# electron_v010.net
KiCad netlist of a schematic drawn in EAGLE
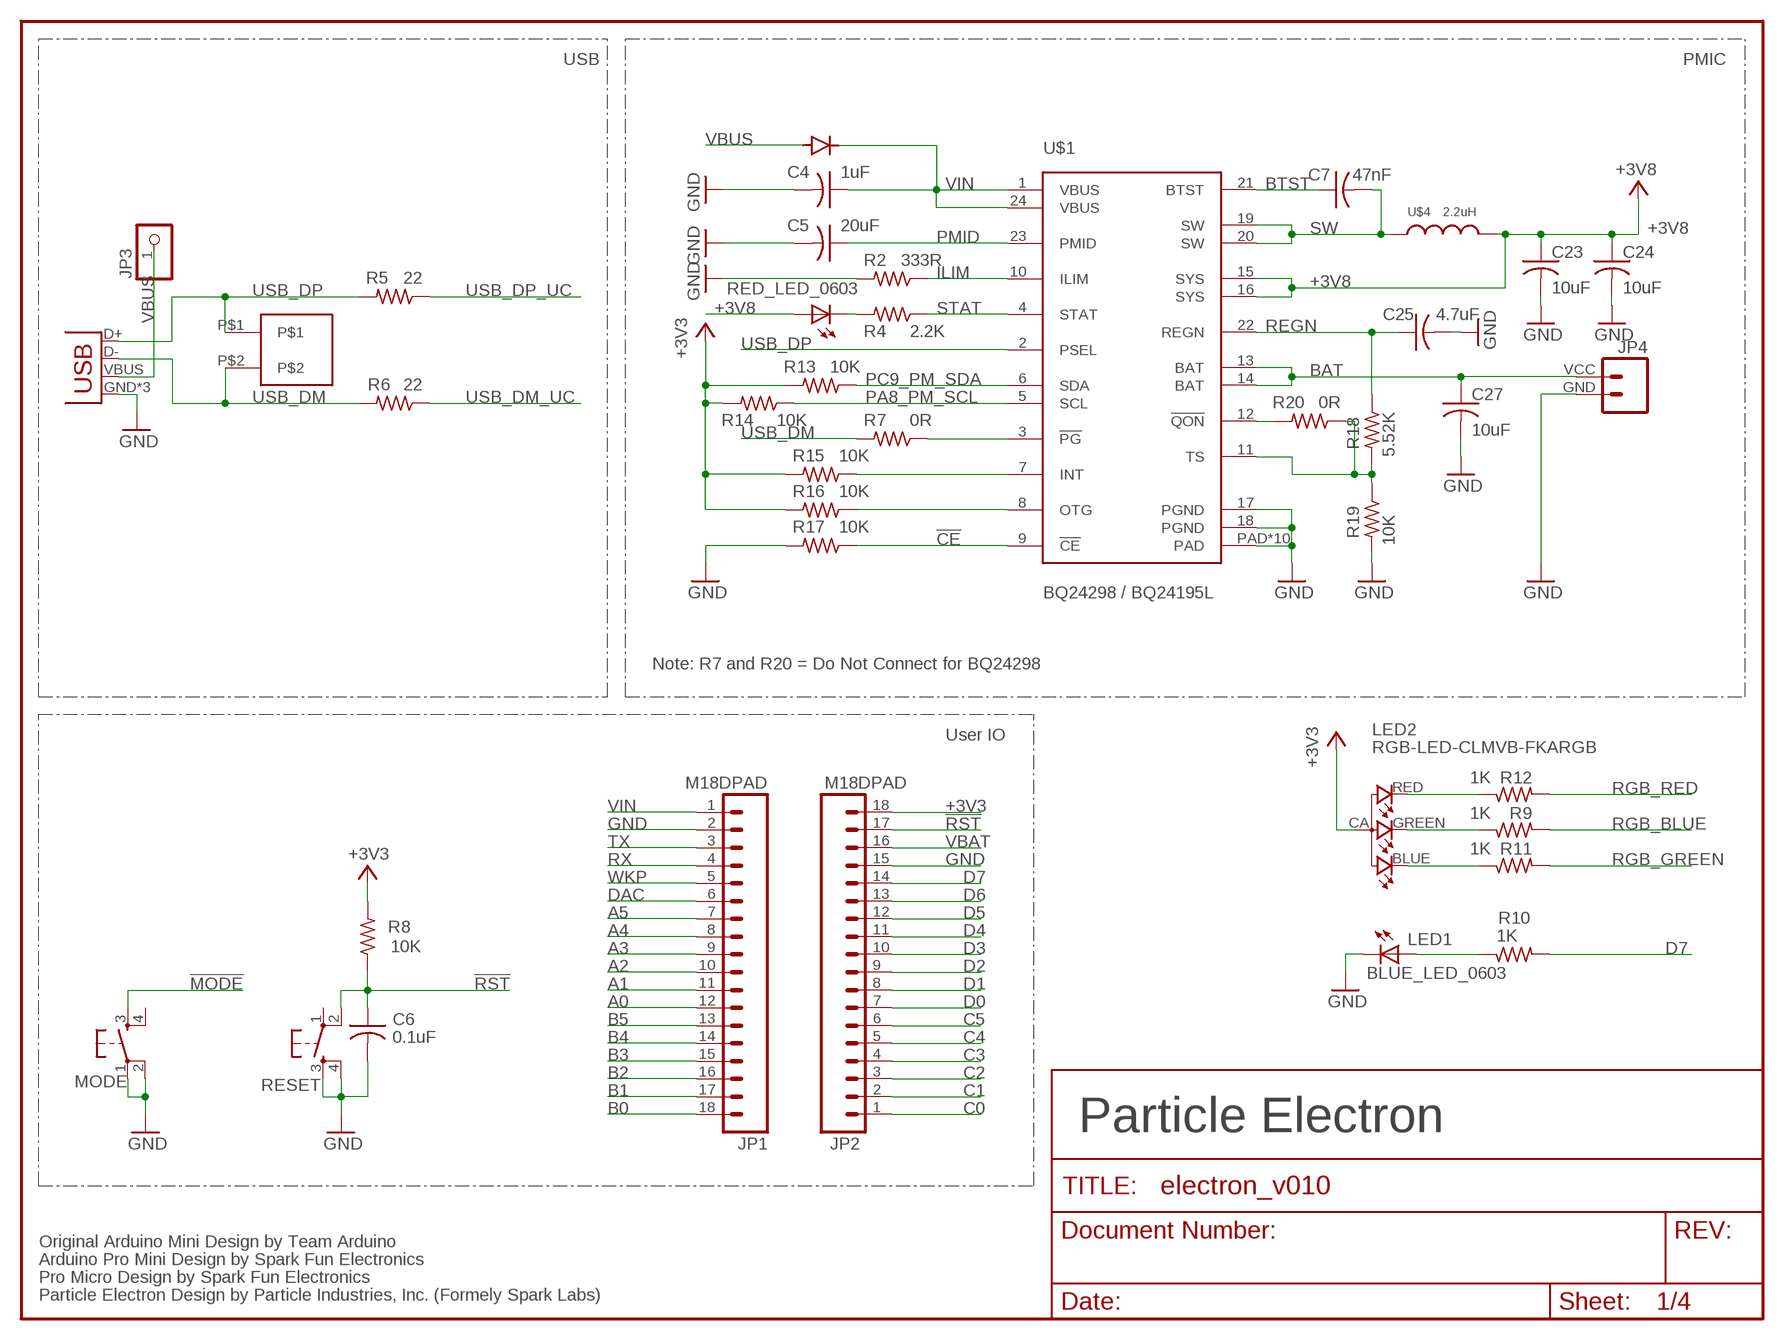
[diagram p0: schematic, sheet 1]
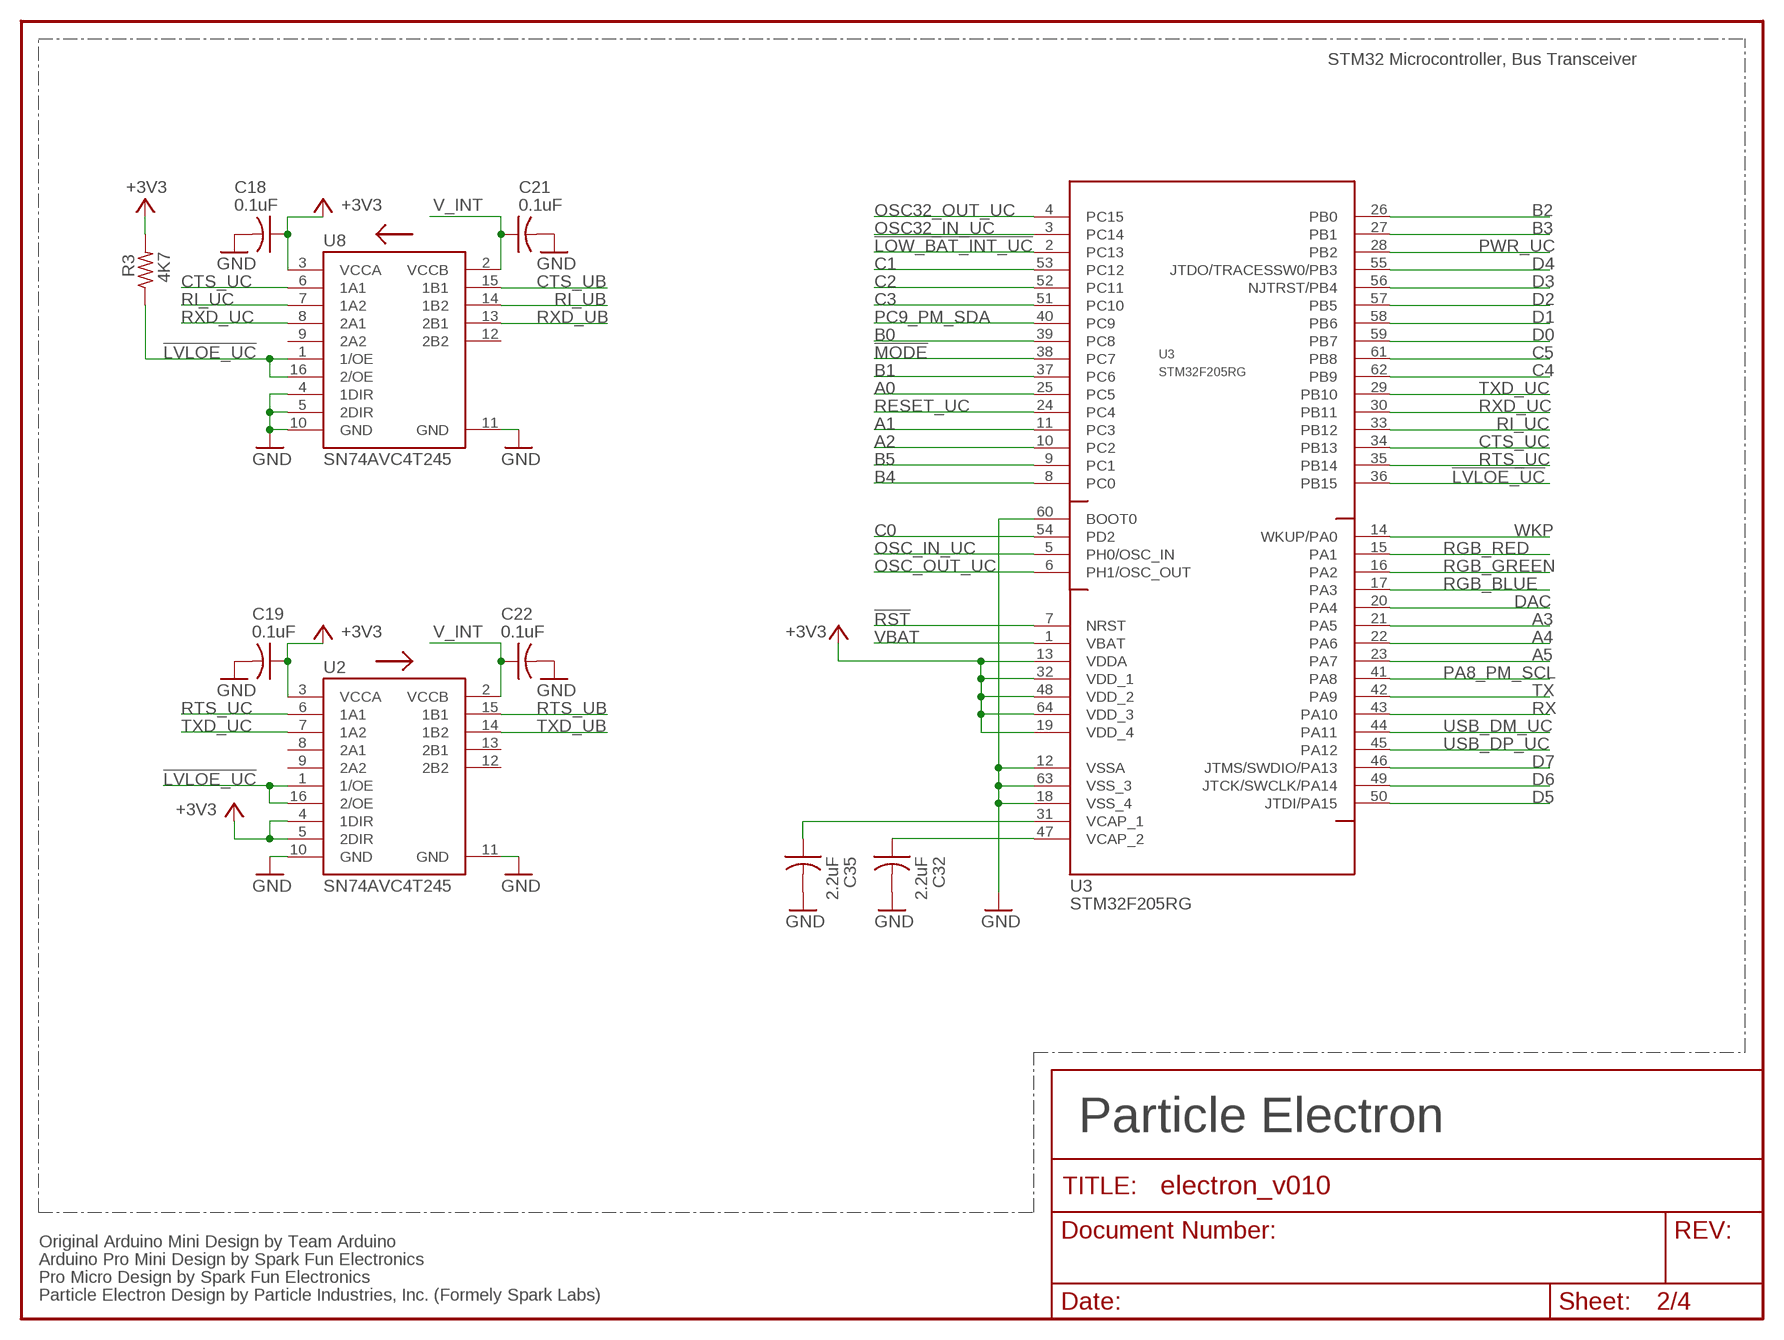
[diagram p1: schematic, sheet 2]
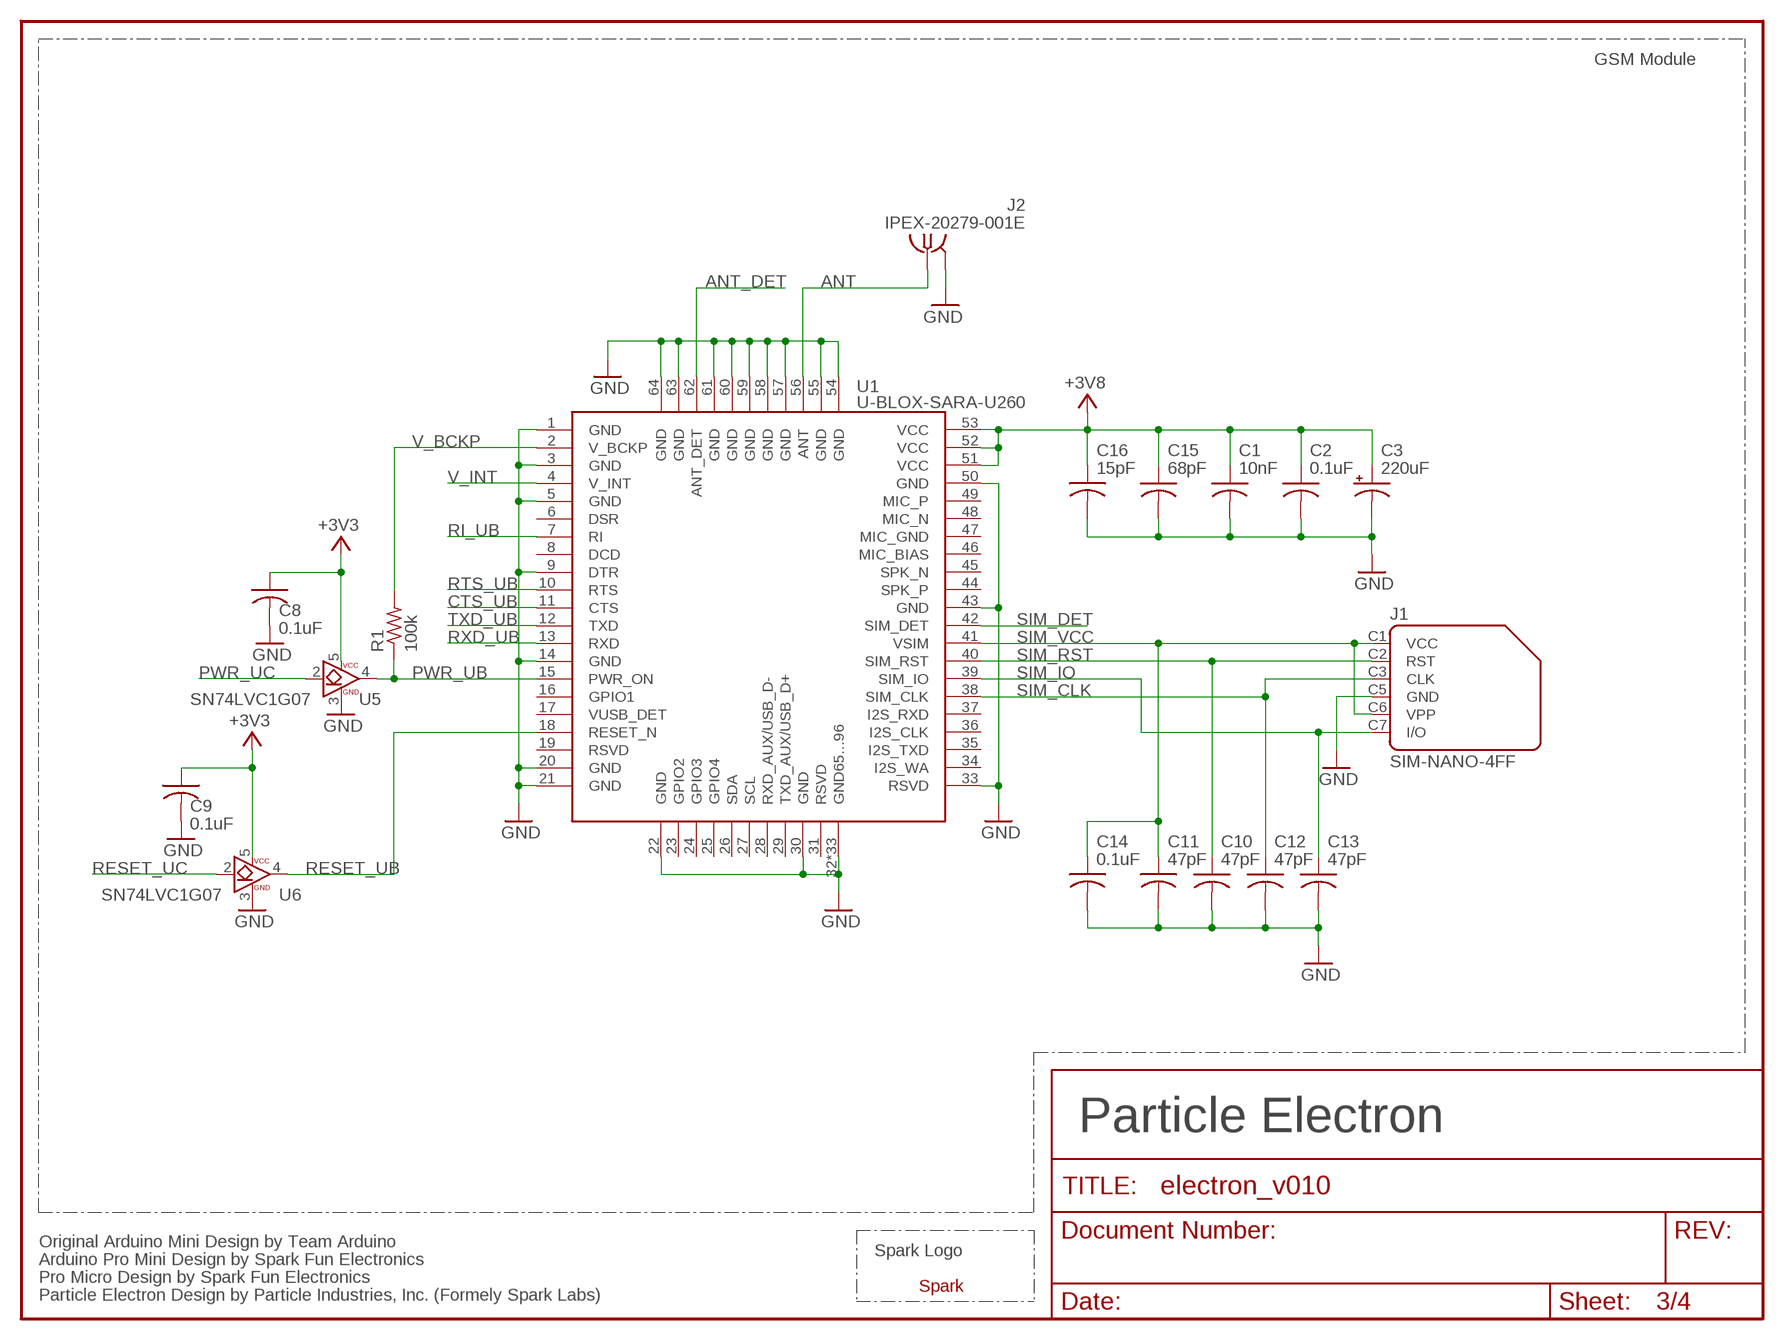
[diagram p2: schematic, sheet 3]
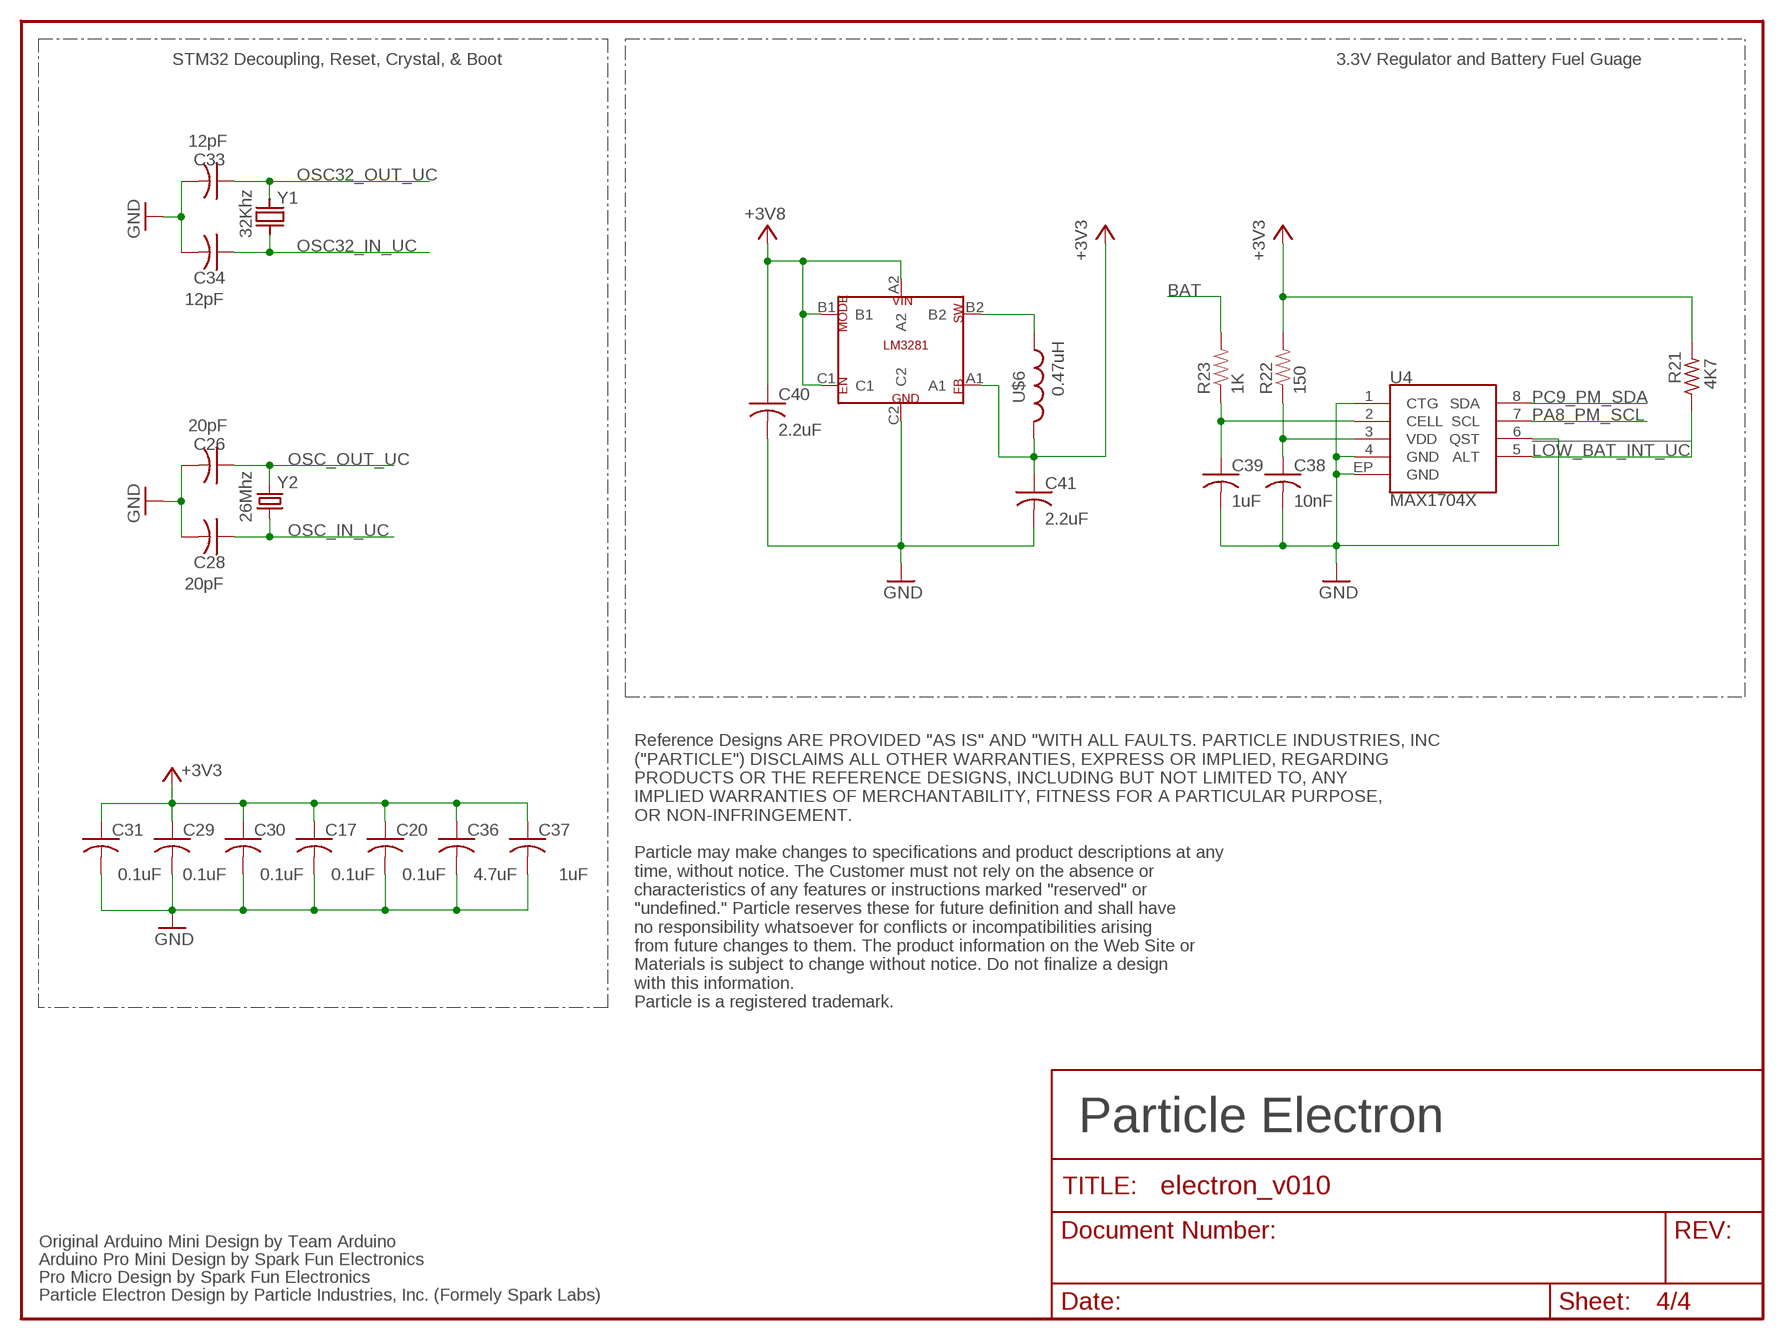
[diagram p3: schematic, sheet 4]

(export (version "E")
  (design (tool "Eeschema 10.0.6"))
  (components
    (comp (ref "C17")
      (value "0.1uF")
      (footprint "eagle-import:C0402_B")
      (libsource (lib "eagle-import") (part "C-US"))
    )
    (comp (ref "C20")
      (value "0.1uF")
      (footprint "eagle-import:C0402_B")
      (libsource (lib "eagle-import") (part "C-US"))
    )
    (comp (ref "C26")
      (value "20pF")
      (footprint "eagle-import:C0402_B")
      (libsource (lib "eagle-import") (part "C-US"))
    )
    (comp (ref "C28")
      (value "20pF")
      (footprint "eagle-import:C0402_B")
      (libsource (lib "eagle-import") (part "C-US"))
    )
    (comp (ref "C29")
      (value "0.1uF")
      (footprint "eagle-import:C0402_B")
      (libsource (lib "eagle-import") (part "C-US"))
    )
    (comp (ref "C30")
      (value "0.1uF")
      (footprint "eagle-import:C0402_B")
      (libsource (lib "eagle-import") (part "C-US"))
    )
    (comp (ref "C31")
      (value "0.1uF")
      (footprint "eagle-import:C0402_B")
      (libsource (lib "eagle-import") (part "C-US"))
    )
    (comp (ref "C33")
      (value "12pF")
      (footprint "eagle-import:C0402_B")
      (libsource (lib "eagle-import") (part "C-US"))
    )
    (comp (ref "C34")
      (value "12pF")
      (footprint "eagle-import:C0402_B")
      (libsource (lib "eagle-import") (part "C-US"))
    )
    (comp (ref "C36")
      (value "4.7uF")
      (footprint "eagle-import:C0402_B")
      (libsource (lib "eagle-import") (part "C-US"))
    )
    (comp (ref "C37")
      (value "1uF")
      (footprint "eagle-import:C0402_B")
      (libsource (lib "eagle-import") (part "C-US"))
    )
    (comp (ref "C38")
      (value "10nF")
      (footprint "eagle-import:C0402_B")
      (libsource (lib "eagle-import") (part "C-US"))
    )
    (comp (ref "C39")
      (value "1uF")
      (footprint "eagle-import:C0402_B")
      (libsource (lib "eagle-import") (part "C-US"))
    )
    (comp (ref "C40")
      (value "2.2uF")
      (footprint "eagle-import:C0603_B")
      (libsource (lib "eagle-import") (part "C-US0603"))
    )
    (comp (ref "C41")
      (value "2.2uF")
      (footprint "eagle-import:C0603_B")
      (libsource (lib "eagle-import") (part "C-US0603"))
    )
    (comp (ref "R21")
      (value "4K7")
      (footprint "eagle-import:R0402_B")
      (libsource (lib "eagle-import") (part "R-US_"))
    )
    (comp (ref "R22")
      (value "150")
      (footprint "eagle-import:0603-RES")
      (libsource (lib "eagle-import") (part "RESISTOR0603-RES"))
    )
    (comp (ref "R23")
      (value "1K")
      (footprint "eagle-import:0603-RES")
      (libsource (lib "eagle-import") (part "RESISTOR0603-RES"))
    )
    (comp (ref "U$5")
      (value "LM3281_DSBGA")
      (footprint "eagle-import:DSBGA")
      (libsource (lib "eagle-import") (part "LM3281_DSBGA"))
    )
    (comp (ref "U$6")
      (value "0.47uH")
      (footprint "eagle-import:INDUCTOR-0805")
      (libsource (lib "eagle-import") (part "INDUCTORG"))
    )
    (comp (ref "U4")
      (value "MAX1704X")
      (footprint "eagle-import:TDFN-8")
      (libsource (lib "eagle-import") (part "MAX1704X"))
    )
    (comp (ref "Y1")
      (value "32Khz")
      (footprint "eagle-import:FC135")
      (libsource (lib "eagle-import") (part "Q_FC135"))
    )
    (comp (ref "Y2")
      (value "26Mhz")
      (footprint "eagle-import:CRYSTAL-SMD-5X3")
      (libsource (lib "eagle-import") (part "CRYSTAL5X3"))
    )
    (comp (ref "C1")
      (value "10nF")
      (footprint "eagle-import:C0402_B")
      (libsource (lib "eagle-import") (part "C-US"))
    )
    (comp (ref "C2")
      (value "0.1uF")
      (footprint "eagle-import:C0402_B")
      (libsource (lib "eagle-import") (part "C-US"))
    )
    (comp (ref "C3")
      (value "220uF")
      (footprint "eagle-import:C_6032-28R")
      (libsource (lib "eagle-import") (part "CPOL-USC/6032-28R"))
    )
    (comp (ref "C8")
      (value "0.1uF")
      (footprint "eagle-import:C0402_B")
      (libsource (lib "eagle-import") (part "C-US"))
    )
    (comp (ref "C9")
      (value "0.1uF")
      (footprint "eagle-import:C0402_B")
      (libsource (lib "eagle-import") (part "C-US"))
    )
    (comp (ref "C10")
      (value "47pF")
      (footprint "eagle-import:C0402_B")
      (libsource (lib "eagle-import") (part "C-US"))
    )
    (comp (ref "C11")
      (value "47pF")
      (footprint "eagle-import:C0402_B")
      (libsource (lib "eagle-import") (part "C-US"))
    )
    (comp (ref "C12")
      (value "47pF")
      (footprint "eagle-import:C0402_B")
      (libsource (lib "eagle-import") (part "C-US"))
    )
    (comp (ref "C13")
      (value "47pF")
      (footprint "eagle-import:C0402_B")
      (libsource (lib "eagle-import") (part "C-US"))
    )
    (comp (ref "C14")
      (value "0.1uF")
      (footprint "eagle-import:C0402_B")
      (libsource (lib "eagle-import") (part "C-US"))
    )
    (comp (ref "C15")
      (value "68pF")
      (footprint "eagle-import:C0402_B")
      (libsource (lib "eagle-import") (part "C-US"))
    )
    (comp (ref "C16")
      (value "15pF")
      (footprint "eagle-import:C0402_B")
      (libsource (lib "eagle-import") (part "C-US"))
    )
    (comp (ref "J1")
      (value "SIM-NANO-4FF")
      (footprint "eagle-import:GCT-SIM8100")
      (libsource (lib "eagle-import") (part "SIM-NANO-4FF"))
    )
    (comp (ref "J2")
      (value "IPEX-20279-001E")
      (footprint "eagle-import:IPEX-20279-001E")
      (libsource (lib "eagle-import") (part "IPEX-20279-001E"))
    )
    (comp (ref "R1")
      (value "100k")
      (footprint "eagle-import:R0402_B")
      (libsource (lib "eagle-import") (part "R-US_"))
    )
    (comp (ref "U$2")
      (value "SPARK_LOGO2")
      (footprint "eagle-import:SPARK_LOGO2")
      (libsource (lib "eagle-import") (part "SPARK_LOGO2"))
    )
    (comp (ref "U1")
      (value "U-BLOX-SARA-U260")
      (footprint "eagle-import:U-BLOX-SARA-U2")
      (libsource (lib "eagle-import") (part "U-BLOX-SARA-U260"))
    )
    (comp (ref "U5")
      (value "SN74LVC1G07")
      (footprint "eagle-import:SC-70-5")
      (libsource (lib "eagle-import") (part "SN74LVC1G07"))
    )
    (comp (ref "U6")
      (value "SN74LVC1G07")
      (footprint "eagle-import:SC-70-5")
      (libsource (lib "eagle-import") (part "SN74LVC1G07"))
    )
    (comp (ref "C18")
      (value "0.1uF")
      (footprint "eagle-import:C0402_B")
      (libsource (lib "eagle-import") (part "C-US"))
    )
    (comp (ref "C19")
      (value "0.1uF")
      (footprint "eagle-import:C0402_B")
      (libsource (lib "eagle-import") (part "C-US"))
    )
    (comp (ref "C21")
      (value "0.1uF")
      (footprint "eagle-import:C0402_B")
      (libsource (lib "eagle-import") (part "C-US"))
    )
    (comp (ref "C22")
      (value "0.1uF")
      (footprint "eagle-import:C0402_B")
      (libsource (lib "eagle-import") (part "C-US"))
    )
    (comp (ref "C32")
      (value "2.2uF")
      (footprint "eagle-import:C0402_B")
      (libsource (lib "eagle-import") (part "C-US"))
    )
    (comp (ref "C35")
      (value "2.2uF")
      (footprint "eagle-import:C0402_B")
      (libsource (lib "eagle-import") (part "C-US"))
    )
    (comp (ref "R3")
      (value "4K7")
      (footprint "eagle-import:R0402_B")
      (libsource (lib "eagle-import") (part "R-US_"))
    )
    (comp (ref "U2")
      (value "SN74AVC4T245")
      (footprint "eagle-import:UFQFN-16")
      (libsource (lib "eagle-import") (part "SN74AVC4T245"))
    )
    (comp (ref "U3")
      (value "STM32F205RG")
      (footprint "eagle-import:LQFP64")
      (libsource (lib "eagle-import") (part "STM32F20XR"))
    )
    (comp (ref "U8")
      (value "SN74AVC4T245")
      (footprint "eagle-import:UFQFN-16")
      (libsource (lib "eagle-import") (part "SN74AVC4T245"))
    )
    (comp (ref "BLUE_LED_0603")
      (value "LED0603")
      (footprint "eagle-import:LED-0603")
      (libsource (lib "eagle-import") (part "LED0603"))
    )
    (comp (ref "C4")
      (value "1uF")
      (footprint "eagle-import:C0603_B")
      (libsource (lib "eagle-import") (part "C-US0603"))
    )
    (comp (ref "C5")
      (value "20uF")
      (footprint "eagle-import:C0603_B")
      (libsource (lib "eagle-import") (part "C-US0603"))
    )
    (comp (ref "C6")
      (value "0.1uF")
      (footprint "eagle-import:C0402_B")
      (libsource (lib "eagle-import") (part "C-US"))
    )
    (comp (ref "C7")
      (value "47nF")
      (footprint "eagle-import:C0402_B")
      (libsource (lib "eagle-import") (part "C-US"))
    )
    (comp (ref "C23")
      (value "10uF")
      (footprint "eagle-import:C0603_B")
      (libsource (lib "eagle-import") (part "C-US0603"))
    )
    (comp (ref "C24")
      (value "10uF")
      (footprint "eagle-import:C0603_B")
      (libsource (lib "eagle-import") (part "C-US0603"))
    )
    (comp (ref "C25")
      (value "4.7uF")
      (footprint "eagle-import:C0603_B")
      (libsource (lib "eagle-import") (part "C-US0603"))
    )
    (comp (ref "C27")
      (value "10uF")
      (footprint "eagle-import:C0603_B")
      (libsource (lib "eagle-import") (part "C-US0603"))
    )
    (comp (ref "JP1")
      (value "M18DPAD")
      (footprint "eagle-import:1X18-D-PADS")
      (libsource (lib "eagle-import") (part "M18DPAD"))
    )
    (comp (ref "JP2")
      (value "M18DPAD")
      (footprint "eagle-import:1X18-D-PADS")
      (libsource (lib "eagle-import") (part "M18DPAD"))
    )
    (comp (ref "JP3")
      (value "PINHD-1X1")
      (footprint "eagle-import:1X01")
      (libsource (lib "eagle-import") (part "PINHD-1X1"))
    )
    (comp (ref "JP4")
      (value "M024UCON-15767")
      (footprint "eagle-import:JST-2-SMD-VERT")
      (libsource (lib "eagle-import") (part "M024UCON-15767"))
    )
    (comp (ref "LED2")
      (value "RGB-LED-CLMVB-FKARGB")
      (footprint "eagle-import:PLCC4-2MM-RGB")
      (libsource (lib "eagle-import") (part "RGB-LED-CLMVB-FKARGB"))
    )
    (comp (ref "MODE")
      (value "KMR211GLFS")
      (footprint "eagle-import:TACTILE_SWITCH_SMD")
      (libsource (lib "eagle-import") (part "TAC_SWITCHSMD"))
    )
    (comp (ref "R2")
      (value "333R")
      (footprint "eagle-import:R0402_B")
      (libsource (lib "eagle-import") (part "R-US_"))
    )
    (comp (ref "R4")
      (value "2.2K")
      (footprint "eagle-import:R0402_B")
      (libsource (lib "eagle-import") (part "R-US_"))
    )
    (comp (ref "R5")
      (value "22")
      (footprint "eagle-import:R0402_B")
      (libsource (lib "eagle-import") (part "R-US_"))
    )
    (comp (ref "R6")
      (value "22")
      (footprint "eagle-import:R0402_B")
      (libsource (lib "eagle-import") (part "R-US_"))
    )
    (comp (ref "R7")
      (value "0R")
      (footprint "eagle-import:R0402_B")
      (libsource (lib "eagle-import") (part "R-US_"))
    )
    (comp (ref "R8")
      (value "10K")
      (footprint "eagle-import:R0402_B")
      (libsource (lib "eagle-import") (part "R-US_"))
    )
    (comp (ref "R9")
      (value "1K")
      (footprint "eagle-import:R0402_B")
      (libsource (lib "eagle-import") (part "R-US_"))
    )
    (comp (ref "R10")
      (value "1K")
      (footprint "eagle-import:R0402_B")
      (libsource (lib "eagle-import") (part "R-US_"))
    )
    (comp (ref "R11")
      (value "1K")
      (footprint "eagle-import:R0402_B")
      (libsource (lib "eagle-import") (part "R-US_"))
    )
    (comp (ref "R12")
      (value "1K")
      (footprint "eagle-import:R0402_B")
      (libsource (lib "eagle-import") (part "R-US_"))
    )
    (comp (ref "R13")
      (value "10K")
      (footprint "eagle-import:R0402_B")
      (libsource (lib "eagle-import") (part "R-US_"))
    )
    (comp (ref "R14")
      (value "10K")
      (footprint "eagle-import:R0402_B")
      (libsource (lib "eagle-import") (part "R-US_"))
    )
    (comp (ref "R15")
      (value "10K")
      (footprint "eagle-import:R0402_B")
      (libsource (lib "eagle-import") (part "R-US_"))
    )
    (comp (ref "R16")
      (value "10K")
      (footprint "eagle-import:R0402_B")
      (libsource (lib "eagle-import") (part "R-US_"))
    )
    (comp (ref "R17")
      (value "10K")
      (footprint "eagle-import:R0402_B")
      (libsource (lib "eagle-import") (part "R-US_"))
    )
    (comp (ref "R18")
      (value "5.52K")
      (footprint "eagle-import:R0402_B")
      (libsource (lib "eagle-import") (part "R-US_"))
    )
    (comp (ref "R19")
      (value "10K")
      (footprint "eagle-import:R0402_B")
      (libsource (lib "eagle-import") (part "R-US_"))
    )
    (comp (ref "R20")
      (value "0R")
      (footprint "eagle-import:R0402_B")
      (libsource (lib "eagle-import") (part "R-US_"))
    )
    (comp (ref "RED_LED_0603")
      (value "LED0603")
      (footprint "eagle-import:LED-0603")
      (libsource (lib "eagle-import") (part "LED0603"))
    )
    (comp (ref "RESET")
      (value "KMR211GLFS")
      (footprint "eagle-import:TACTILE_SWITCH_SMD")
      (libsource (lib "eagle-import") (part "TAC_SWITCHSMD"))
    )
    (comp (ref "U$1")
      (value "BQ24298 / BQ24195L")
      (footprint "eagle-import:QFN24")
      (libsource (lib "eagle-import") (part "BQ24298RTWR"))
    )
    (comp (ref "U$3")
      (value "DIODE")
      (footprint "eagle-import:DIODE-DO-220AA(SMP)")
      (libsource (lib "eagle-import") (part "DIODE"))
    )
    (comp (ref "U$4")
      (value "2.2uH")
      (footprint "eagle-import:INDUCTOR-4020")
      (libsource (lib "eagle-import") (part "INDUCTORH"))
    )
    (comp (ref "U$7")
      (value "M02_0.05_HEADER")
      (footprint "eagle-import:M02_0.05_HEADER")
      (libsource (lib "eagle-import") (part "M02_0.05_HEADER"))
    )
    (comp (ref "X1")
      (value "USB-MICROB")
      (footprint "eagle-import:USB-MICROB-SLOT-HOLE")
      (libsource (lib "eagle-import") (part "USBUSB-MICROB-SLOT-HOLE"))
    )
  )
  (nets
    (net (code "1") (name "+3V3") (class "Default")
      (node (ref "C17") (pin "1") (pinfunction "1_1") (pintype "passive"))
      (node (ref "C18") (pin "1") (pinfunction "1_1") (pintype "passive"))
      (node (ref "C19") (pin "1") (pinfunction "1_1") (pintype "passive"))
      (node (ref "C20") (pin "1") (pinfunction "1_1") (pintype "passive"))
      (node (ref "C29") (pin "1") (pinfunction "1_1") (pintype "passive"))
      (node (ref "C30") (pin "1") (pinfunction "1_1") (pintype "passive"))
      (node (ref "C31") (pin "1") (pinfunction "1_1") (pintype "passive"))
      (node (ref "C36") (pin "1") (pinfunction "1_1") (pintype "passive"))
      (node (ref "C37") (pin "1") (pinfunction "1_1") (pintype "passive"))
      (node (ref "C41") (pin "1") (pinfunction "1_1") (pintype "passive"))
      (node (ref "C8") (pin "1") (pinfunction "1_1") (pintype "passive"))
      (node (ref "C9") (pin "1") (pinfunction "1_1") (pintype "passive"))
      (node (ref "JP2") (pin "18") (pinfunction "18_18") (pintype "passive"))
      (node (ref "LED2") (pin "CA") (pinfunction "1_CA") (pintype "passive"))
      (node (ref "R13") (pin "2") (pinfunction "2_2") (pintype "passive"))
      (node (ref "R14") (pin "2") (pinfunction "2_2") (pintype "passive"))
      (node (ref "R15") (pin "2") (pinfunction "2_2") (pintype "passive"))
      (node (ref "R16") (pin "2") (pinfunction "2_2") (pintype "passive"))
      (node (ref "R21") (pin "2") (pinfunction "2_2") (pintype "passive"))
      (node (ref "R22") (pin "2") (pinfunction "2_2") (pintype "passive"))
      (node (ref "R3") (pin "2") (pinfunction "2_2") (pintype "passive"))
      (node (ref "R8") (pin "2") (pinfunction "2_2") (pintype "passive"))
      (node (ref "U$5") (pin "A1") (pinfunction "A1_A1") (pintype "bidirectional"))
      (node (ref "U$6") (pin "2") (pinfunction "2_2") (pintype "passive"))
      (node (ref "U2") (pin "3") (pinfunction "VCCA_3") (pintype "bidirectional"))
      (node (ref "U2") (pin "4") (pinfunction "1DIR_4") (pintype "bidirectional"))
      (node (ref "U2") (pin "5") (pinfunction "2DIR_5") (pintype "bidirectional"))
      (node (ref "U3") (pin "13") (pinfunction "VDDA_13") (pintype "power_in"))
      (node (ref "U3") (pin "19") (pinfunction "VDD_4_19") (pintype "power_in"))
      (node (ref "U3") (pin "32") (pinfunction "VDD_1_32") (pintype "power_in"))
      (node (ref "U3") (pin "48") (pinfunction "VDD_2_48") (pintype "power_in"))
      (node (ref "U3") (pin "64") (pinfunction "VDD_3_64") (pintype "power_in"))
      (node (ref "U5") (pin "5") (pinfunction "VCC_5") (pintype "bidirectional"))
      (node (ref "U6") (pin "5") (pinfunction "VCC_5") (pintype "bidirectional"))
      (node (ref "U8") (pin "3") (pinfunction "VCCA_3") (pintype "bidirectional"))
    )
    (net (code "2") (name "+3V8") (class "Default")
      (node (ref "C1") (pin "1") (pinfunction "1_1") (pintype "passive"))
      (node (ref "C15") (pin "1") (pinfunction "1_1") (pintype "passive"))
      (node (ref "C16") (pin "1") (pinfunction "1_1") (pintype "passive"))
      (node (ref "C2") (pin "1") (pinfunction "1_1") (pintype "passive"))
      (node (ref "C23") (pin "1") (pinfunction "1_1") (pintype "passive"))
      (node (ref "C24") (pin "1") (pinfunction "1_1") (pintype "passive"))
      (node (ref "C3") (pin "+") (pinfunction "+_+") (pintype "passive"))
      (node (ref "C40") (pin "1") (pinfunction "1_1") (pintype "passive"))
      (node (ref "RED_LED_0603") (pin "A") (pinfunction "A_A") (pintype "passive"))
      (node (ref "U$1") (pin "15") (pinfunction "SYS_15") (pintype "power_in"))
      (node (ref "U$1") (pin "16") (pinfunction "SYS_16") (pintype "power_in"))
      (node (ref "U$4") (pin "P$2") (pinfunction "2_P$2") (pintype "passive"))
      (node (ref "U$5") (pin "A2") (pinfunction "A2_A2") (pintype "bidirectional"))
      (node (ref "U$5") (pin "B1") (pinfunction "B1_B1") (pintype "bidirectional"))
      (node (ref "U$5") (pin "C1") (pinfunction "C1_C1") (pintype "bidirectional"))
      (node (ref "U1") (pin "51") (pinfunction "VCC_51") (pintype "bidirectional"))
      (node (ref "U1") (pin "52") (pinfunction "VCC_52") (pintype "bidirectional"))
      (node (ref "U1") (pin "53") (pinfunction "VCC_53") (pintype "bidirectional"))
    )
    (net (code "3") (name "A0") (class "Default")
      (node (ref "JP1") (pin "12") (pinfunction "12_12") (pintype "passive"))
      (node (ref "U3") (pin "25") (pinfunction "PC5_25") (pintype "bidirectional"))
    )
    (net (code "4") (name "A1") (class "Default")
      (node (ref "JP1") (pin "11") (pinfunction "11_11") (pintype "passive"))
      (node (ref "U3") (pin "11") (pinfunction "PC3_11") (pintype "bidirectional"))
    )
    (net (code "5") (name "A2") (class "Default")
      (node (ref "JP1") (pin "10") (pinfunction "10_10") (pintype "passive"))
      (node (ref "U3") (pin "10") (pinfunction "PC2_10") (pintype "bidirectional"))
    )
    (net (code "6") (name "A3") (class "Default")
      (node (ref "JP1") (pin "9") (pinfunction "9_9") (pintype "passive"))
      (node (ref "U3") (pin "21") (pinfunction "PA5_21") (pintype "bidirectional"))
    )
    (net (code "7") (name "A4") (class "Default")
      (node (ref "JP1") (pin "8") (pinfunction "8_8") (pintype "passive"))
      (node (ref "U3") (pin "22") (pinfunction "PA6_22") (pintype "bidirectional"))
    )
    (net (code "8") (name "A5") (class "Default")
      (node (ref "JP1") (pin "7") (pinfunction "7_7") (pintype "passive"))
      (node (ref "U3") (pin "23") (pinfunction "PA7_23") (pintype "bidirectional"))
    )
    (net (code "9") (name "ANT") (class "Default")
      (node (ref "J2") (pin "1") (pinfunction "1_1") (pintype "passive"))
      (node (ref "U1") (pin "56") (pinfunction "ANT_56") (pintype "bidirectional"))
    )
    (net (code "10") (name "ANT_DET") (class "Default")
      (node (ref "U1") (pin "62") (pinfunction "ANT_DET_62") (pintype "bidirectional"))
    )
    (net (code "11") (name "B0") (class "Default")
      (node (ref "JP1") (pin "18") (pinfunction "18_18") (pintype "passive"))
      (node (ref "U3") (pin "39") (pinfunction "PC8_39") (pintype "bidirectional"))
    )
    (net (code "12") (name "B1") (class "Default")
      (node (ref "JP1") (pin "17") (pinfunction "17_17") (pintype "passive"))
      (node (ref "U3") (pin "37") (pinfunction "PC6_37") (pintype "bidirectional"))
    )
    (net (code "13") (name "B2") (class "Default")
      (node (ref "JP1") (pin "16") (pinfunction "16_16") (pintype "passive"))
      (node (ref "U3") (pin "26") (pinfunction "PB0_26") (pintype "bidirectional"))
    )
    (net (code "14") (name "B3") (class "Default")
      (node (ref "JP1") (pin "15") (pinfunction "15_15") (pintype "passive"))
      (node (ref "U3") (pin "27") (pinfunction "PB1_27") (pintype "bidirectional"))
    )
    (net (code "15") (name "B4") (class "Default")
      (node (ref "JP1") (pin "14") (pinfunction "14_14") (pintype "passive"))
      (node (ref "U3") (pin "8") (pinfunction "PC0_8") (pintype "bidirectional"))
    )
    (net (code "16") (name "B5") (class "Default")
      (node (ref "JP1") (pin "13") (pinfunction "13_13") (pintype "passive"))
      (node (ref "U3") (pin "9") (pinfunction "PC1_9") (pintype "bidirectional"))
    )
    (net (code "17") (name "BAT") (class "Default")
      (node (ref "C27") (pin "1") (pinfunction "1_1") (pintype "passive"))
      (node (ref "JP4") (pin "VCC") (pinfunction "2_VCC") (pintype "passive"))
      (node (ref "R23") (pin "2") (pinfunction "2_2") (pintype "passive"))
      (node (ref "U$1") (pin "13") (pinfunction "BAT_13") (pintype "passive"))
      (node (ref "U$1") (pin "14") (pinfunction "BAT_14") (pintype "power_in"))
    )
    (net (code "18") (name "BTST") (class "Default")
      (node (ref "C7") (pin "1") (pinfunction "1_1") (pintype "passive"))
      (node (ref "U$1") (pin "21") (pinfunction "BTST_21") (pintype "bidirectional"))
    )
    (net (code "19") (name "C0") (class "Default")
      (node (ref "JP2") (pin "1") (pinfunction "1_1") (pintype "passive"))
      (node (ref "U3") (pin "54") (pinfunction "PD2_54") (pintype "bidirectional"))
    )
    (net (code "20") (name "C1") (class "Default")
      (node (ref "JP2") (pin "2") (pinfunction "2_2") (pintype "passive"))
      (node (ref "U3") (pin "53") (pinfunction "PC12_53") (pintype "bidirectional"))
    )
    (net (code "21") (name "C2") (class "Default")
      (node (ref "JP2") (pin "3") (pinfunction "3_3") (pintype "passive"))
      (node (ref "U3") (pin "52") (pinfunction "PC11_52") (pintype "bidirectional"))
    )
    (net (code "22") (name "C3") (class "Default")
      (node (ref "JP2") (pin "4") (pinfunction "4_4") (pintype "passive"))
      (node (ref "U3") (pin "51") (pinfunction "PC10_51") (pintype "bidirectional"))
    )
    (net (code "23") (name "C4") (class "Default")
      (node (ref "JP2") (pin "5") (pinfunction "5_5") (pintype "passive"))
      (node (ref "U3") (pin "62") (pinfunction "PB9_62") (pintype "bidirectional"))
    )
    (net (code "24") (name "C5") (class "Default")
      (node (ref "JP2") (pin "6") (pinfunction "6_6") (pintype "passive"))
      (node (ref "U3") (pin "61") (pinfunction "PB8_61") (pintype "bidirectional"))
    )
    (net (code "25") (name "CTS_UB") (class "Default")
      (node (ref "U1") (pin "11") (pinfunction "CTS_11") (pintype "bidirectional"))
      (node (ref "U8") (pin "15") (pinfunction "1B1_15") (pintype "bidirectional"))
    )
    (net (code "26") (name "CTS_UC") (class "Default")
      (node (ref "U3") (pin "34") (pinfunction "PB13_34") (pintype "bidirectional"))
      (node (ref "U8") (pin "6") (pinfunction "1A1_6") (pintype "bidirectional"))
    )
    (net (code "27") (name "D0") (class "Default")
      (node (ref "JP2") (pin "7") (pinfunction "7_7") (pintype "passive"))
      (node (ref "U3") (pin "59") (pinfunction "PB7_59") (pintype "bidirectional"))
    )
    (net (code "28") (name "D1") (class "Default")
      (node (ref "JP2") (pin "8") (pinfunction "8_8") (pintype "passive"))
      (node (ref "U3") (pin "58") (pinfunction "PB6_58") (pintype "bidirectional"))
    )
    (net (code "29") (name "D2") (class "Default")
      (node (ref "JP2") (pin "9") (pinfunction "9_9") (pintype "passive"))
      (node (ref "U3") (pin "57") (pinfunction "PB5_57") (pintype "bidirectional"))
    )
    (net (code "30") (name "D3") (class "Default")
      (node (ref "JP2") (pin "10") (pinfunction "10_10") (pintype "passive"))
      (node (ref "U3") (pin "56") (pinfunction "NJTRST/PB4_56") (pintype "bidirectional"))
    )
    (net (code "31") (name "D4") (class "Default")
      (node (ref "JP2") (pin "11") (pinfunction "11_11") (pintype "passive"))
      (node (ref "U3") (pin "55") (pinfunction "JTDO/TRACESSW0/PB3_55") (pintype "bidirectional"))
    )
    (net (code "32") (name "D5") (class "Default")
      (node (ref "JP2") (pin "12") (pinfunction "12_12") (pintype "passive"))
      (node (ref "U3") (pin "50") (pinfunction "JTDI/PA15_50") (pintype "bidirectional"))
    )
    (net (code "33") (name "D6") (class "Default")
      (node (ref "JP2") (pin "13") (pinfunction "13_13") (pintype "passive"))
      (node (ref "U3") (pin "49") (pinfunction "JTCK/SWCLK/PA14_49") (pintype "bidirectional"))
    )
    (net (code "34") (name "D7") (class "Default")
      (node (ref "JP2") (pin "14") (pinfunction "14_14") (pintype "passive"))
      (node (ref "R10") (pin "2") (pinfunction "2_2") (pintype "passive"))
      (node (ref "U3") (pin "46") (pinfunction "JTMS/SWDIO/PA13_46") (pintype "bidirectional"))
    )
    (net (code "35") (name "DAC") (class "Default")
      (node (ref "JP1") (pin "6") (pinfunction "6_6") (pintype "passive"))
      (node (ref "U3") (pin "20") (pinfunction "PA4_20") (pintype "bidirectional"))
    )
    (net (code "36") (name "GND") (class "Default")
      (node (ref "BLUE_LED_0603") (pin "C") (pinfunction "C_C") (pintype "passive"))
      (node (ref "C1") (pin "2") (pinfunction "2_2") (pintype "passive"))
      (node (ref "C10") (pin "2") (pinfunction "2_2") (pintype "passive"))
      (node (ref "C11") (pin "2") (pinfunction "2_2") (pintype "passive"))
      (node (ref "C12") (pin "2") (pinfunction "2_2") (pintype "passive"))
      (node (ref "C13") (pin "2") (pinfunction "2_2") (pintype "passive"))
      (node (ref "C14") (pin "2") (pinfunction "2_2") (pintype "passive"))
      (node (ref "C15") (pin "2") (pinfunction "2_2") (pintype "passive"))
      (node (ref "C16") (pin "2") (pinfunction "2_2") (pintype "passive"))
      (node (ref "C17") (pin "2") (pinfunction "2_2") (pintype "passive"))
      (node (ref "C18") (pin "2") (pinfunction "2_2") (pintype "passive"))
      (node (ref "C19") (pin "2") (pinfunction "2_2") (pintype "passive"))
      (node (ref "C2") (pin "2") (pinfunction "2_2") (pintype "passive"))
      (node (ref "C20") (pin "2") (pinfunction "2_2") (pintype "passive"))
      (node (ref "C21") (pin "2") (pinfunction "2_2") (pintype "passive"))
      (node (ref "C22") (pin "2") (pinfunction "2_2") (pintype "passive"))
      (node (ref "C23") (pin "2") (pinfunction "2_2") (pintype "passive"))
      (node (ref "C24") (pin "2") (pinfunction "2_2") (pintype "passive"))
      (node (ref "C25") (pin "2") (pinfunction "2_2") (pintype "passive"))
      (node (ref "C26") (pin "2") (pinfunction "2_2") (pintype "passive"))
      (node (ref "C27") (pin "2") (pinfunction "2_2") (pintype "passive"))
      (node (ref "C28") (pin "2") (pinfunction "2_2") (pintype "passive"))
      (node (ref "C29") (pin "2") (pinfunction "2_2") (pintype "passive"))
      (node (ref "C3") (pin "-") (pinfunction "-_-") (pintype "passive"))
      (node (ref "C30") (pin "2") (pinfunction "2_2") (pintype "passive"))
      (node (ref "C31") (pin "2") (pinfunction "2_2") (pintype "passive"))
      (node (ref "C32") (pin "2") (pinfunction "2_2") (pintype "passive"))
      (node (ref "C33") (pin "2") (pinfunction "2_2") (pintype "passive"))
      (node (ref "C34") (pin "2") (pinfunction "2_2") (pintype "passive"))
      (node (ref "C35") (pin "2") (pinfunction "2_2") (pintype "passive"))
      (node (ref "C36") (pin "2") (pinfunction "2_2") (pintype "passive"))
      (node (ref "C37") (pin "2") (pinfunction "2_2") (pintype "passive"))
      (node (ref "C38") (pin "2") (pinfunction "2_2") (pintype "passive"))
      (node (ref "C39") (pin "2") (pinfunction "2_2") (pintype "passive"))
      (node (ref "C4") (pin "2") (pinfunction "2_2") (pintype "passive"))
      (node (ref "C40") (pin "2") (pinfunction "2_2") (pintype "passive"))
      (node (ref "C41") (pin "2") (pinfunction "2_2") (pintype "passive"))
      (node (ref "C5") (pin "2") (pinfunction "2_2") (pintype "passive"))
      (node (ref "C6") (pin "2") (pinfunction "2_2") (pintype "passive"))
      (node (ref "C8") (pin "2") (pinfunction "2_2") (pintype "passive"))
      (node (ref "C9") (pin "2") (pinfunction "2_2") (pintype "passive"))
      (node (ref "J1") (pin "C5") (pinfunction "GND_C5") (pintype "passive"))
      (node (ref "J2") (pin "2@1") (pinfunction "GND_2@1") (pintype "passive"))
      (node (ref "J2") (pin "2@2") (pinfunction "GND_2@2") (pintype "passive"))
      (node (ref "JP1") (pin "2") (pinfunction "2_2") (pintype "passive"))
      (node (ref "JP2") (pin "15") (pinfunction "15_15") (pintype "passive"))
      (node (ref "JP4") (pin "GND") (pinfunction "1_GND") (pintype "passive"))
      (node (ref "MODE") (pin "1") (pinfunction "1_1") (pintype "passive"))
      (node (ref "MODE") (pin "2") (pinfunction "2_2") (pintype "passive"))
      (node (ref "R17") (pin "2") (pinfunction "2_2") (pintype "passive"))
      (node (ref "R19") (pin "2") (pinfunction "2_2") (pintype "passive"))
      (node (ref "R2") (pin "2") (pinfunction "2_2") (pintype "passive"))
      (node (ref "RESET") (pin "3") (pinfunction "3_3") (pintype "passive"))
      (node (ref "RESET") (pin "4") (pinfunction "4_4") (pintype "passive"))
      (node (ref "U$1") (pin "17") (pinfunction "PGND_17") (pintype "passive"))
      (node (ref "U$1") (pin "18") (pinfunction "PGND_18") (pintype "passive"))
      (node (ref "U$1") (pin "PAD") (pinfunction "PAD_PAD") (pintype "power_in"))
      (node (ref "U$1") (pin "PAD@1") (pinfunction "PAD_PAD@1") (pintype "power_in"))
      (node (ref "U$1") (pin "PAD@2") (pinfunction "PAD_PAD@2") (pintype "power_in"))
      (node (ref "U$1") (pin "PAD@3") (pinfunction "PAD_PAD@3") (pintype "power_in"))
      (node (ref "U$1") (pin "PAD@4") (pinfunction "PAD_PAD@4") (pintype "power_in"))
      (node (ref "U$1") (pin "PAD@5") (pinfunction "PAD_PAD@5") (pintype "power_in"))
      (node (ref "U$1") (pin "PAD@6") (pinfunction "PAD_PAD@6") (pintype "power_in"))
      (node (ref "U$1") (pin "PAD@7") (pinfunction "PAD_PAD@7") (pintype "power_in"))
      (node (ref "U$1") (pin "PAD@8") (pinfunction "PAD_PAD@8") (pintype "power_in"))
      (node (ref "U$1") (pin "PAD@9") (pinfunction "PAD_PAD@9") (pintype "power_in"))
      (node (ref "U$5") (pin "C2") (pinfunction "C2_C2") (pintype "bidirectional"))
      (node (ref "U1") (pin "1") (pinfunction "GND_1") (pintype "bidirectional"))
      (node (ref "U1") (pin "14") (pinfunction "GND_14") (pintype "bidirectional"))
      (node (ref "U1") (pin "20") (pinfunction "GND_20") (pintype "bidirectional"))
      (node (ref "U1") (pin "21") (pinfunction "GND_21") (pintype "bidirectional"))
      (node (ref "U1") (pin "22") (pinfunction "GND_22") (pintype "bidirectional"))
      (node (ref "U1") (pin "3") (pinfunction "GND_3") (pintype "bidirectional"))
      (node (ref "U1") (pin "30") (pinfunction "GND_30") (pintype "bidirectional"))
      (node (ref "U1") (pin "32") (pinfunction "GND65...96_32") (pintype "bidirectional"))
      (node (ref "U1") (pin "33") (pinfunction "RSVD_33") (pintype "bidirectional"))
      (node (ref "U1") (pin "43") (pinfunction "GND_43") (pintype "bidirectional"))
      (node (ref "U1") (pin "5") (pinfunction "GND_5") (pintype "bidirectional"))
      (node (ref "U1") (pin "50") (pinfunction "GND_50") (pintype "bidirectional"))
      (node (ref "U1") (pin "54") (pinfunction "GND_54") (pintype "bidirectional"))
      (node (ref "U1") (pin "55") (pinfunction "GND_55") (pintype "bidirectional"))
      (node (ref "U1") (pin "57") (pinfunction "GND_57") (pintype "bidirectional"))
      (node (ref "U1") (pin "58") (pinfunction "GND_58") (pintype "bidirectional"))
      (node (ref "U1") (pin "59") (pinfunction "GND_59") (pintype "bidirectional"))
      (node (ref "U1") (pin "60") (pinfunction "GND_60") (pintype "bidirectional"))
      (node (ref "U1") (pin "61") (pinfunction "GND_61") (pintype "bidirectional"))
      (node (ref "U1") (pin "63") (pinfunction "GND_63") (pintype "bidirectional"))
      (node (ref "U1") (pin "64") (pinfunction "GND_64") (pintype "bidirectional"))
      (node (ref "U1") (pin "65") (pinfunction "GND65...96_65") (pintype "bidirectional"))
      (node (ref "U1") (pin "66") (pinfunction "GND65...96_66") (pintype "bidirectional"))
      (node (ref "U1") (pin "67") (pinfunction "GND65...96_67") (pintype "bidirectional"))
      (node (ref "U1") (pin "68") (pinfunction "GND65...96_68") (pintype "bidirectional"))
      (node (ref "U1") (pin "69") (pinfunction "GND65...96_69") (pintype "bidirectional"))
      (node (ref "U1") (pin "70") (pinfunction "GND65...96_70") (pintype "bidirectional"))
      (node (ref "U1") (pin "71") (pinfunction "GND65...96_71") (pintype "bidirectional"))
      (node (ref "U1") (pin "72") (pinfunction "GND65...96_72") (pintype "bidirectional"))
      (node (ref "U1") (pin "73") (pinfunction "GND65...96_73") (pintype "bidirectional"))
      (node (ref "U1") (pin "74") (pinfunction "GND65...96_74") (pintype "bidirectional"))
      (node (ref "U1") (pin "75") (pinfunction "GND65...96_75") (pintype "bidirectional"))
      (node (ref "U1") (pin "76") (pinfunction "GND65...96_76") (pintype "bidirectional"))
      (node (ref "U1") (pin "77") (pinfunction "GND65...96_77") (pintype "bidirectional"))
      (node (ref "U1") (pin "78") (pinfunction "GND65...96_78") (pintype "bidirectional"))
      (node (ref "U1") (pin "79") (pinfunction "GND65...96_79") (pintype "bidirectional"))
      (node (ref "U1") (pin "80") (pinfunction "GND65...96_80") (pintype "bidirectional"))
      (node (ref "U1") (pin "81") (pinfunction "GND65...96_81") (pintype "bidirectional"))
      (node (ref "U1") (pin "82") (pinfunction "GND65...96_82") (pintype "bidirectional"))
      (node (ref "U1") (pin "83") (pinfunction "GND65...96_83") (pintype "bidirectional"))
      (node (ref "U1") (pin "84") (pinfunction "GND65...96_84") (pintype "bidirectional"))
      (node (ref "U1") (pin "85") (pinfunction "GND65...96_85") (pintype "bidirectional"))
      (node (ref "U1") (pin "86") (pinfunction "GND65...96_86") (pintype "bidirectional"))
      (node (ref "U1") (pin "87") (pinfunction "GND65...96_87") (pintype "bidirectional"))
      (node (ref "U1") (pin "88") (pinfunction "GND65...96_88") (pintype "bidirectional"))
      (node (ref "U1") (pin "89") (pinfunction "GND65...96_89") (pintype "bidirectional"))
      (node (ref "U1") (pin "9") (pinfunction "DTR_9") (pintype "bidirectional"))
      (node (ref "U1") (pin "90") (pinfunction "GND65...96_90") (pintype "bidirectional"))
      (node (ref "U1") (pin "91") (pinfunction "GND65...96_91") (pintype "bidirectional"))
      (node (ref "U1") (pin "92") (pinfunction "GND65...96_92") (pintype "bidirectional"))
      (node (ref "U1") (pin "93") (pinfunction "GND65...96_93") (pintype "bidirectional"))
      (node (ref "U1") (pin "94") (pinfunction "GND65...96_94") (pintype "bidirectional"))
      (node (ref "U1") (pin "95") (pinfunction "GND65...96_95") (pintype "bidirectional"))
      (node (ref "U1") (pin "96") (pinfunction "GND65...96_96") (pintype "bidirectional"))
      (node (ref "U2") (pin "10") (pinfunction "GND_10") (pintype "bidirectional"))
      (node (ref "U2") (pin "11") (pinfunction "GND_11") (pintype "bidirectional"))
      (node (ref "U3") (pin "12") (pinfunction "VSSA_12") (pintype "power_in"))
      (node (ref "U3") (pin "18") (pinfunction "VSS_4_18") (pintype "power_in"))
      (node (ref "U3") (pin "60") (pinfunction "BOOT0_60") (pintype "bidirectional"))
      (node (ref "U3") (pin "63") (pinfunction "VSS_3_63") (pintype "power_in"))
      (node (ref "U4") (pin "1") (pinfunction "CTG_1") (pintype "bidirectional"))
      (node (ref "U4") (pin "4") (pinfunction "GND_4") (pintype "bidirectional"))
      (node (ref "U4") (pin "6") (pinfunction "QST_6") (pintype "bidirectional"))
      (node (ref "U4") (pin "EP") (pinfunction "GND_EP") (pintype "bidirectional"))
      (node (ref "U5") (pin "3") (pinfunction "GND_3") (pintype "bidirectional"))
      (node (ref "U6") (pin "3") (pinfunction "GND_3") (pintype "bidirectional"))
      (node (ref "U8") (pin "10") (pinfunction "GND_10") (pintype "bidirectional"))
      (node (ref "U8") (pin "11") (pinfunction "GND_11") (pintype "bidirectional"))
      (node (ref "U8") (pin "4") (pinfunction "1DIR_4") (pintype "bidirectional"))
      (node (ref "U8") (pin "5") (pinfunction "2DIR_5") (pintype "bidirectional"))
      (node (ref "X1") (pin "GND") (pinfunction "GND_GND") (pintype "bidirectional"))
      (node (ref "X1") (pin "MT1") (pinfunction "GND_MT1") (pintype "bidirectional"))
      (node (ref "X1") (pin "MT2") (pinfunction "GND_MT2") (pintype "bidirectional"))
    )
    (net (code "37") (name "ILIM") (class "Default")
      (node (ref "R2") (pin "1") (pinfunction "1_1") (pintype "passive"))
      (node (ref "U$1") (pin "10") (pinfunction "ILIM_10") (pintype "output"))
    )
    (net (code "38") (name "LED1") (class "Default")
      (node (ref "BLUE_LED_0603") (pin "A") (pinfunction "A_A") (pintype "passive"))
      (node (ref "R10") (pin "1") (pinfunction "1_1") (pintype "passive"))
    )
    (net (code "39") (name "Net-(LED2-2)") (class "Default")
      (node (ref "LED2") (pin "BLUE") (pinfunction "2_BLUE") (pintype "passive"))
      (node (ref "R11") (pin "1") (pinfunction "1_1") (pintype "passive"))
    )
    (net (code "40") (name "Net-(LED2-3)") (class "Default")
      (node (ref "LED2") (pin "GREEN") (pinfunction "3_GREEN") (pintype "passive"))
      (node (ref "R9") (pin "1") (pinfunction "1_1") (pintype "passive"))
    )
    (net (code "41") (name "Net-(LED2-4)") (class "Default")
      (node (ref "LED2") (pin "RED") (pinfunction "4_RED") (pintype "passive"))
      (node (ref "R12") (pin "1") (pinfunction "1_1") (pintype "passive"))
    )
    (net (code "42") (name "Net-(R4-Pad2)") (class "Default")
      (node (ref "R4") (pin "2") (pinfunction "2_2") (pintype "passive"))
      (node (ref "RED_LED_0603") (pin "C") (pinfunction "C_C") (pintype "passive"))
    )
    (net (code "43") (name "Net-(U$1-INT)") (class "Default")
      (node (ref "R15") (pin "1") (pinfunction "1_1") (pintype "passive"))
      (node (ref "U$1") (pin "7") (pinfunction "INT_7") (pintype "bidirectional"))
    )
    (net (code "44") (name "Net-(U$1-OTG)") (class "Default")
      (node (ref "R16") (pin "1") (pinfunction "1_1") (pintype "passive"))
      (node (ref "U$1") (pin "8") (pinfunction "OTG_8") (pintype "bidirectional"))
    )
    (net (code "45") (name "Net-(U$1-TS)") (class "Default")
      (node (ref "R18") (pin "2") (pinfunction "2_2") (pintype "passive"))
      (node (ref "R19") (pin "1") (pinfunction "1_1") (pintype "passive"))
      (node (ref "R20") (pin "1") (pinfunction "1_1") (pintype "passive"))
      (node (ref "U$1") (pin "11") (pinfunction "TS_11") (pintype "bidirectional"))
    )
    (net (code "46") (name "Net-(U$1-~{PG})") (class "Default")
      (node (ref "R7") (pin "1") (pinfunction "1_1") (pintype "passive"))
      (node (ref "U$1") (pin "3") (pinfunction "~{PG}_3") (pintype "output"))
    )
    (net (code "47") (name "Net-(U$1-~{QON})") (class "Default")
      (node (ref "R20") (pin "2") (pinfunction "2_2") (pintype "passive"))
      (node (ref "U$1") (pin "12") (pinfunction "~{QON}_12") (pintype "bidirectional"))
    )
    (net (code "48") (name "Net-(U$5-PadB2)") (class "Default")
      (node (ref "U$5") (pin "B2") (pinfunction "B2_B2") (pintype "bidirectional"))
      (node (ref "U$6") (pin "1") (pinfunction "1_1") (pintype "passive"))
    )
    (net (code "49") (name "Net-(U3-VCAP_1)") (class "Default")
      (node (ref "C35") (pin "1") (pinfunction "1_1") (pintype "passive"))
      (node (ref "U3") (pin "31") (pinfunction "VCAP_1_31") (pintype "power_in"))
    )
    (net (code "50") (name "Net-(U3-VCAP_2)") (class "Default")
      (node (ref "C32") (pin "1") (pinfunction "1_1") (pintype "passive"))
      (node (ref "U3") (pin "47") (pinfunction "VCAP_2_47") (pintype "power_in"))
    )
    (net (code "51") (name "Net-(U4-CELL)") (class "Default")
      (node (ref "C39") (pin "1") (pinfunction "1_1") (pintype "passive"))
      (node (ref "R23") (pin "1") (pinfunction "1_1") (pintype "passive"))
      (node (ref "U4") (pin "2") (pinfunction "CELL_2") (pintype "bidirectional"))
    )
    (net (code "52") (name "Net-(U4-VDD)") (class "Default")
      (node (ref "C38") (pin "1") (pinfunction "1_1") (pintype "passive"))
      (node (ref "R22") (pin "1") (pinfunction "1_1") (pintype "passive"))
      (node (ref "U4") (pin "3") (pinfunction "VDD_3") (pintype "bidirectional"))
    )
    (net (code "53") (name "OSC32_IN_UC") (class "Default")
      (node (ref "C34") (pin "1") (pinfunction "1_1") (pintype "passive"))
      (node (ref "U3") (pin "3") (pinfunction "PC14_3") (pintype "bidirectional"))
      (node (ref "Y1") (pin "X1") (pinfunction "1_X1") (pintype "passive"))
    )
    (net (code "54") (name "OSC32_OUT_UC") (class "Default")
      (node (ref "C33") (pin "1") (pinfunction "1_1") (pintype "passive"))
      (node (ref "U3") (pin "4") (pinfunction "PC15_4") (pintype "bidirectional"))
      (node (ref "Y1") (pin "X2") (pinfunction "2_X2") (pintype "passive"))
    )
    (net (code "55") (name "OSC_IN_UC") (class "Default")
      (node (ref "C28") (pin "1") (pinfunction "1_1") (pintype "passive"))
      (node (ref "U3") (pin "5") (pinfunction "PH0/OSC_IN_5") (pintype "bidirectional"))
      (node (ref "Y2") (pin "1") (pinfunction "1_1") (pintype "passive"))
    )
    (net (code "56") (name "OSC_OUT_UC") (class "Default")
      (node (ref "C26") (pin "1") (pinfunction "1_1") (pintype "passive"))
      (node (ref "U3") (pin "6") (pinfunction "PH1/OSC_OUT_6") (pintype "bidirectional"))
      (node (ref "Y2") (pin "3") (pinfunction "2_3") (pintype "passive"))
    )
    (net (code "57") (name "PA8_PM_SCL") (class "Default")
      (node (ref "R14") (pin "1") (pinfunction "1_1") (pintype "passive"))
      (node (ref "U$1") (pin "5") (pinfunction "SCL_5") (pintype "output"))
      (node (ref "U3") (pin "41") (pinfunction "PA8_41") (pintype "bidirectional"))
      (node (ref "U4") (pin "7") (pinfunction "SCL_7") (pintype "bidirectional"))
    )
    (net (code "58") (name "PC9_PM_SDA") (class "Default")
      (node (ref "R13") (pin "1") (pinfunction "1_1") (pintype "passive"))
      (node (ref "U$1") (pin "6") (pinfunction "SDA_6") (pintype "bidirectional"))
      (node (ref "U3") (pin "40") (pinfunction "PC9_40") (pintype "bidirectional"))
      (node (ref "U4") (pin "8") (pinfunction "SDA_8") (pintype "bidirectional"))
    )
    (net (code "59") (name "PMID") (class "Default")
      (node (ref "C5") (pin "1") (pinfunction "1_1") (pintype "passive"))
      (node (ref "U$1") (pin "23") (pinfunction "PMID_23") (pintype "passive"))
    )
    (net (code "60") (name "PWR_UB") (class "Default")
      (node (ref "R1") (pin "1") (pinfunction "1_1") (pintype "passive"))
      (node (ref "U1") (pin "15") (pinfunction "PWR_ON_15") (pintype "bidirectional"))
      (node (ref "U5") (pin "4") (pinfunction "B_4") (pintype "bidirectional"))
    )
    (net (code "61") (name "PWR_UC") (class "Default")
      (node (ref "U3") (pin "28") (pinfunction "PB2_28") (pintype "bidirectional"))
      (node (ref "U5") (pin "2") (pinfunction "A_2") (pintype "bidirectional"))
    )
    (net (code "62") (name "REGN") (class "Default")
      (node (ref "C25") (pin "1") (pinfunction "1_1") (pintype "passive"))
      (node (ref "R18") (pin "1") (pinfunction "1_1") (pintype "passive"))
      (node (ref "U$1") (pin "22") (pinfunction "REGN_22") (pintype "bidirectional"))
    )
    (net (code "63") (name "RESET_UB") (class "Default")
      (node (ref "U1") (pin "18") (pinfunction "RESET_N_18") (pintype "bidirectional"))
      (node (ref "U6") (pin "4") (pinfunction "B_4") (pintype "bidirectional"))
    )
    (net (code "64") (name "RESET_UC") (class "Default")
      (node (ref "U3") (pin "24") (pinfunction "PC4_24") (pintype "bidirectional"))
      (node (ref "U6") (pin "2") (pinfunction "A_2") (pintype "bidirectional"))
    )
    (net (code "65") (name "RGB_BLUE") (class "Default")
      (node (ref "R11") (pin "2") (pinfunction "2_2") (pintype "passive"))
      (node (ref "U3") (pin "17") (pinfunction "PA3_17") (pintype "bidirectional"))
    )
    (net (code "66") (name "RGB_GREEN") (class "Default")
      (node (ref "R9") (pin "2") (pinfunction "2_2") (pintype "passive"))
      (node (ref "U3") (pin "16") (pinfunction "PA2_16") (pintype "bidirectional"))
    )
    (net (code "67") (name "RGB_RED") (class "Default")
      (node (ref "R12") (pin "2") (pinfunction "2_2") (pintype "passive"))
      (node (ref "U3") (pin "15") (pinfunction "PA1_15") (pintype "bidirectional"))
    )
    (net (code "68") (name "RI_UB") (class "Default")
      (node (ref "U1") (pin "7") (pinfunction "RI_7") (pintype "bidirectional"))
      (node (ref "U8") (pin "14") (pinfunction "1B2_14") (pintype "bidirectional"))
    )
    (net (code "69") (name "RI_UC") (class "Default")
      (node (ref "U3") (pin "33") (pinfunction "PB12_33") (pintype "bidirectional"))
      (node (ref "U8") (pin "7") (pinfunction "1A2_7") (pintype "bidirectional"))
    )
    (net (code "70") (name "RTS_UB") (class "Default")
      (node (ref "U1") (pin "10") (pinfunction "RTS_10") (pintype "bidirectional"))
      (node (ref "U2") (pin "15") (pinfunction "1B1_15") (pintype "bidirectional"))
    )
    (net (code "71") (name "RTS_UC") (class "Default")
      (node (ref "U2") (pin "6") (pinfunction "1A1_6") (pintype "bidirectional"))
      (node (ref "U3") (pin "35") (pinfunction "PB14_35") (pintype "bidirectional"))
    )
    (net (code "72") (name "RX") (class "Default")
      (node (ref "JP1") (pin "4") (pinfunction "4_4") (pintype "passive"))
      (node (ref "U3") (pin "43") (pinfunction "PA10_43") (pintype "bidirectional"))
    )
    (net (code "73") (name "RXD_UB") (class "Default")
      (node (ref "U1") (pin "13") (pinfunction "RXD_13") (pintype "bidirectional"))
      (node (ref "U8") (pin "13") (pinfunction "2B1_13") (pintype "bidirectional"))
    )
    (net (code "74") (name "RXD_UC") (class "Default")
      (node (ref "U3") (pin "30") (pinfunction "PB11_30") (pintype "bidirectional"))
      (node (ref "U8") (pin "8") (pinfunction "2A1_8") (pintype "bidirectional"))
    )
    (net (code "75") (name "SIM_CLK") (class "Default")
      (node (ref "C12") (pin "1") (pinfunction "1_1") (pintype "passive"))
      (node (ref "J1") (pin "C3") (pinfunction "CLK_C3") (pintype "passive"))
      (node (ref "U1") (pin "38") (pinfunction "SIM_CLK_38") (pintype "bidirectional"))
    )
    (net (code "76") (name "SIM_DET") (class "Default")
      (node (ref "U1") (pin "42") (pinfunction "SIM_DET_42") (pintype "bidirectional"))
    )
    (net (code "77") (name "SIM_IO") (class "Default")
      (node (ref "C13") (pin "1") (pinfunction "1_1") (pintype "passive"))
      (node (ref "J1") (pin "C7") (pinfunction "I/O_C7") (pintype "passive"))
      (node (ref "U1") (pin "39") (pinfunction "SIM_IO_39") (pintype "bidirectional"))
    )
    (net (code "78") (name "SIM_RST") (class "Default")
      (node (ref "C10") (pin "1") (pinfunction "1_1") (pintype "passive"))
      (node (ref "J1") (pin "C2") (pinfunction "RST_C2") (pintype "passive"))
      (node (ref "U1") (pin "40") (pinfunction "SIM_RST_40") (pintype "bidirectional"))
    )
    (net (code "79") (name "SIM_VCC") (class "Default")
      (node (ref "C11") (pin "1") (pinfunction "1_1") (pintype "passive"))
      (node (ref "C14") (pin "1") (pinfunction "1_1") (pintype "passive"))
      (node (ref "J1") (pin "C1") (pinfunction "VCC_C1") (pintype "passive"))
      (node (ref "J1") (pin "C6") (pinfunction "VPP_C6") (pintype "passive"))
      (node (ref "U1") (pin "41") (pinfunction "VSIM_41") (pintype "bidirectional"))
    )
    (net (code "80") (name "STAT") (class "Default")
      (node (ref "R4") (pin "1") (pinfunction "1_1") (pintype "passive"))
      (node (ref "U$1") (pin "4") (pinfunction "STAT_4") (pintype "bidirectional"))
    )
    (net (code "81") (name "SW") (class "Default")
      (node (ref "C7") (pin "2") (pinfunction "2_2") (pintype "passive"))
      (node (ref "U$1") (pin "19") (pinfunction "SW_19") (pintype "power_in"))
      (node (ref "U$1") (pin "20") (pinfunction "SW_20") (pintype "power_in"))
      (node (ref "U$4") (pin "P$1") (pinfunction "1_P$1") (pintype "passive"))
    )
    (net (code "82") (name "TX") (class "Default")
      (node (ref "JP1") (pin "3") (pinfunction "3_3") (pintype "passive"))
      (node (ref "U3") (pin "42") (pinfunction "PA9_42") (pintype "bidirectional"))
    )
    (net (code "83") (name "TXD_UB") (class "Default")
      (node (ref "U1") (pin "12") (pinfunction "TXD_12") (pintype "bidirectional"))
      (node (ref "U2") (pin "14") (pinfunction "1B2_14") (pintype "bidirectional"))
    )
    (net (code "84") (name "TXD_UC") (class "Default")
      (node (ref "U2") (pin "7") (pinfunction "1A2_7") (pintype "bidirectional"))
      (node (ref "U3") (pin "29") (pinfunction "PB10_29") (pintype "bidirectional"))
    )
    (net (code "85") (name "USB_DM") (class "Default")
      (node (ref "R6") (pin "2") (pinfunction "2_2") (pintype "passive"))
      (node (ref "R7") (pin "2") (pinfunction "2_2") (pintype "passive"))
      (node (ref "U$7") (pin "P$2") (pinfunction "P$2_P$2") (pintype "bidirectional"))
      (node (ref "X1") (pin "D-") (pinfunction "D-_D-") (pintype "bidirectional"))
    )
    (net (code "86") (name "USB_DM_UC") (class "Default")
      (node (ref "R6") (pin "1") (pinfunction "1_1") (pintype "passive"))
      (node (ref "U3") (pin "44") (pinfunction "PA11_44") (pintype "bidirectional"))
    )
    (net (code "87") (name "USB_DP") (class "Default")
      (node (ref "R5") (pin "2") (pinfunction "2_2") (pintype "passive"))
      (node (ref "U$1") (pin "2") (pinfunction "PSEL_2") (pintype "output"))
      (node (ref "U$7") (pin "P$1") (pinfunction "P$1_P$1") (pintype "bidirectional"))
      (node (ref "X1") (pin "D+") (pinfunction "D+_D+") (pintype "bidirectional"))
    )
    (net (code "88") (name "USB_DP_UC") (class "Default")
      (node (ref "R5") (pin "1") (pinfunction "1_1") (pintype "passive"))
      (node (ref "U3") (pin "45") (pinfunction "PA12_45") (pintype "bidirectional"))
    )
    (net (code "89") (name "VBAT") (class "Default")
      (node (ref "JP2") (pin "16") (pinfunction "16_16") (pintype "passive"))
      (node (ref "U3") (pin "1") (pinfunction "VBAT_1") (pintype "power_in"))
    )
    (net (code "90") (name "VBUS") (class "Default")
      (node (ref "JP3") (pin "1") (pinfunction "1_1") (pintype "passive"))
      (node (ref "U$3") (pin "ANODE") (pinfunction "ANODE_ANODE") (pintype "bidirectional"))
      (node (ref "X1") (pin "VBUS") (pinfunction "VBUS_VBUS") (pintype "bidirectional"))
    )
    (net (code "91") (name "VIN") (class "Default")
      (node (ref "C4") (pin "1") (pinfunction "1_1") (pintype "passive"))
      (node (ref "JP1") (pin "1") (pinfunction "1_1") (pintype "passive"))
      (node (ref "U$1") (pin "1") (pinfunction "VBUS_1") (pintype "power_in"))
      (node (ref "U$1") (pin "24") (pinfunction "VBUS_24") (pintype "passive"))
      (node (ref "U$3") (pin "CATHODE") (pinfunction "CATHODE_CATHODE") (pintype "bidirectional"))
    )
    (net (code "92") (name "V_BCKP") (class "Default")
      (node (ref "R1") (pin "2") (pinfunction "2_2") (pintype "passive"))
      (node (ref "U1") (pin "2") (pinfunction "V_BCKP_2") (pintype "bidirectional"))
    )
    (net (code "93") (name "V_INT") (class "Default")
      (node (ref "C21") (pin "1") (pinfunction "1_1") (pintype "passive"))
      (node (ref "C22") (pin "1") (pinfunction "1_1") (pintype "passive"))
      (node (ref "U1") (pin "4") (pinfunction "V_INT_4") (pintype "bidirectional"))
      (node (ref "U2") (pin "2") (pinfunction "VCCB_2") (pintype "bidirectional"))
      (node (ref "U8") (pin "2") (pinfunction "VCCB_2") (pintype "bidirectional"))
    )
    (net (code "94") (name "WKP") (class "Default")
      (node (ref "JP1") (pin "5") (pinfunction "5_5") (pintype "passive"))
      (node (ref "U3") (pin "14") (pinfunction "WKUP/PA0_14") (pintype "bidirectional"))
    )
    (net (code "95") (name "unconnected-(MODE-Pad4)") (class "Default")
      (node (ref "MODE") (pin "4") (pinfunction "4_4") (pintype "passive"))
    )
    (net (code "96") (name "unconnected-(RESET-Pad1)") (class "Default")
      (node (ref "RESET") (pin "1") (pinfunction "1_1") (pintype "passive"))
    )
    (net (code "97") (name "unconnected-(U1-DCD-Pad8)") (class "Default")
      (node (ref "U1") (pin "8") (pinfunction "DCD_8") (pintype "bidirectional"))
    )
    (net (code "98") (name "unconnected-(U1-DSR-Pad6)") (class "Default")
      (node (ref "U1") (pin "6") (pinfunction "DSR_6") (pintype "bidirectional"))
    )
    (net (code "99") (name "unconnected-(U1-GPIO1-Pad16)") (class "Default")
      (node (ref "U1") (pin "16") (pinfunction "GPIO1_16") (pintype "bidirectional"))
    )
    (net (code "100") (name "unconnected-(U1-GPIO2-Pad23)") (class "Default")
      (node (ref "U1") (pin "23") (pinfunction "GPIO2_23") (pintype "bidirectional"))
    )
    (net (code "101") (name "unconnected-(U1-GPIO3-Pad24)") (class "Default")
      (node (ref "U1") (pin "24") (pinfunction "GPIO3_24") (pintype "bidirectional"))
    )
    (net (code "102") (name "unconnected-(U1-GPIO4-Pad25)") (class "Default")
      (node (ref "U1") (pin "25") (pinfunction "GPIO4_25") (pintype "bidirectional"))
    )
    (net (code "103") (name "unconnected-(U1-I2S_CLK-Pad36)") (class "Default")
      (node (ref "U1") (pin "36") (pinfunction "I2S_CLK_36") (pintype "bidirectional"))
    )
    (net (code "104") (name "unconnected-(U1-I2S_RXD-Pad37)") (class "Default")
      (node (ref "U1") (pin "37") (pinfunction "I2S_RXD_37") (pintype "bidirectional"))
    )
    (net (code "105") (name "unconnected-(U1-I2S_TXD-Pad35)") (class "Default")
      (node (ref "U1") (pin "35") (pinfunction "I2S_TXD_35") (pintype "bidirectional"))
    )
    (net (code "106") (name "unconnected-(U1-I2S_WA-Pad34)") (class "Default")
      (node (ref "U1") (pin "34") (pinfunction "I2S_WA_34") (pintype "bidirectional"))
    )
    (net (code "107") (name "unconnected-(U1-MIC_BIAS-Pad46)") (class "Default")
      (node (ref "U1") (pin "46") (pinfunction "MIC_BIAS_46") (pintype "bidirectional"))
    )
    (net (code "108") (name "unconnected-(U1-MIC_GND-Pad47)") (class "Default")
      (node (ref "U1") (pin "47") (pinfunction "MIC_GND_47") (pintype "bidirectional"))
    )
    (net (code "109") (name "unconnected-(U1-MIC_N-Pad48)") (class "Default")
      (node (ref "U1") (pin "48") (pinfunction "MIC_N_48") (pintype "bidirectional"))
    )
    (net (code "110") (name "unconnected-(U1-MIC_P-Pad49)") (class "Default")
      (node (ref "U1") (pin "49") (pinfunction "MIC_P_49") (pintype "bidirectional"))
    )
    (net (code "111") (name "unconnected-(U1-RSVD-Pad19)") (class "Default")
      (node (ref "U1") (pin "19") (pinfunction "RSVD_19") (pintype "bidirectional"))
    )
    (net (code "112") (name "unconnected-(U1-RSVD-Pad31)") (class "Default")
      (node (ref "U1") (pin "31") (pinfunction "RSVD_31") (pintype "bidirectional"))
    )
    (net (code "113") (name "unconnected-(U1-RXD_AUX{slash}USB_D--Pad28)") (class "Default")
      (node (ref "U1") (pin "28") (pinfunction "RXD_AUX/USB_D-_28") (pintype "bidirectional"))
    )
    (net (code "114") (name "unconnected-(U1-SCL-Pad27)") (class "Default")
      (node (ref "U1") (pin "27") (pinfunction "SCL_27") (pintype "bidirectional"))
    )
    (net (code "115") (name "unconnected-(U1-SDA-Pad26)") (class "Default")
      (node (ref "U1") (pin "26") (pinfunction "SDA_26") (pintype "bidirectional"))
    )
    (net (code "116") (name "unconnected-(U1-SPK_N-Pad45)") (class "Default")
      (node (ref "U1") (pin "45") (pinfunction "SPK_N_45") (pintype "bidirectional"))
    )
    (net (code "117") (name "unconnected-(U1-SPK_P-Pad44)") (class "Default")
      (node (ref "U1") (pin "44") (pinfunction "SPK_P_44") (pintype "bidirectional"))
    )
    (net (code "118") (name "unconnected-(U1-TXD_AUX{slash}USB_D+-Pad29)") (class "Default")
      (node (ref "U1") (pin "29") (pinfunction "TXD_AUX/USB_D+_29") (pintype "bidirectional"))
    )
    (net (code "119") (name "unconnected-(U1-VUSB_DET-Pad17)") (class "Default")
      (node (ref "U1") (pin "17") (pinfunction "VUSB_DET_17") (pintype "bidirectional"))
    )
    (net (code "120") (name "unconnected-(U2-2A1-Pad8)") (class "Default")
      (node (ref "U2") (pin "8") (pinfunction "2A1_8") (pintype "bidirectional"))
    )
    (net (code "121") (name "unconnected-(U2-2A2-Pad9)") (class "Default")
      (node (ref "U2") (pin "9") (pinfunction "2A2_9") (pintype "bidirectional"))
    )
    (net (code "122") (name "unconnected-(U2-2B1-Pad13)") (class "Default")
      (node (ref "U2") (pin "13") (pinfunction "2B1_13") (pintype "bidirectional"))
    )
    (net (code "123") (name "unconnected-(U2-2B2-Pad12)") (class "Default")
      (node (ref "U2") (pin "12") (pinfunction "2B2_12") (pintype "bidirectional"))
    )
    (net (code "124") (name "unconnected-(U8-2A2-Pad9)") (class "Default")
      (node (ref "U8") (pin "9") (pinfunction "2A2_9") (pintype "bidirectional"))
    )
    (net (code "125") (name "unconnected-(U8-2B2-Pad12)") (class "Default")
      (node (ref "U8") (pin "12") (pinfunction "2B2_12") (pintype "bidirectional"))
    )
    (net (code "126") (name "~{CE}") (class "Default")
      (node (ref "R17") (pin "1") (pinfunction "1_1") (pintype "passive"))
      (node (ref "U$1") (pin "9") (pinfunction "~{CE}_9") (pintype "output"))
    )
    (net (code "127") (name "~{LOW_BAT_INT_UC}") (class "Default")
      (node (ref "R21") (pin "1") (pinfunction "1_1") (pintype "passive"))
      (node (ref "U3") (pin "2") (pinfunction "PC13_2") (pintype "bidirectional"))
      (node (ref "U4") (pin "5") (pinfunction "ALT_5") (pintype "bidirectional"))
    )
    (net (code "128") (name "~{LVLOE_UC}") (class "Default")
      (node (ref "R3") (pin "1") (pinfunction "1_1") (pintype "passive"))
      (node (ref "U2") (pin "1") (pinfunction "1/OE_1") (pintype "bidirectional"))
      (node (ref "U2") (pin "16") (pinfunction "2/OE_16") (pintype "bidirectional"))
      (node (ref "U3") (pin "36") (pinfunction "PB15_36") (pintype "bidirectional"))
      (node (ref "U8") (pin "1") (pinfunction "1/OE_1") (pintype "bidirectional"))
      (node (ref "U8") (pin "16") (pinfunction "2/OE_16") (pintype "bidirectional"))
    )
    (net (code "129") (name "~{MODE}") (class "Default")
      (node (ref "MODE") (pin "3") (pinfunction "3_3") (pintype "passive"))
      (node (ref "U3") (pin "38") (pinfunction "PC7_38") (pintype "bidirectional"))
    )
    (net (code "130") (name "~{RST}") (class "Default")
      (node (ref "C6") (pin "1") (pinfunction "1_1") (pintype "passive"))
      (node (ref "JP2") (pin "17") (pinfunction "17_17") (pintype "passive"))
      (node (ref "R8") (pin "1") (pinfunction "1_1") (pintype "passive"))
      (node (ref "RESET") (pin "2") (pinfunction "2_2") (pintype "passive"))
      (node (ref "U3") (pin "7") (pinfunction "NRST_7") (pintype "power_in"))
    )
  )
)
